# TH8_Breakout.net
KiCad netlist of a schematic drawn in Altium Designer
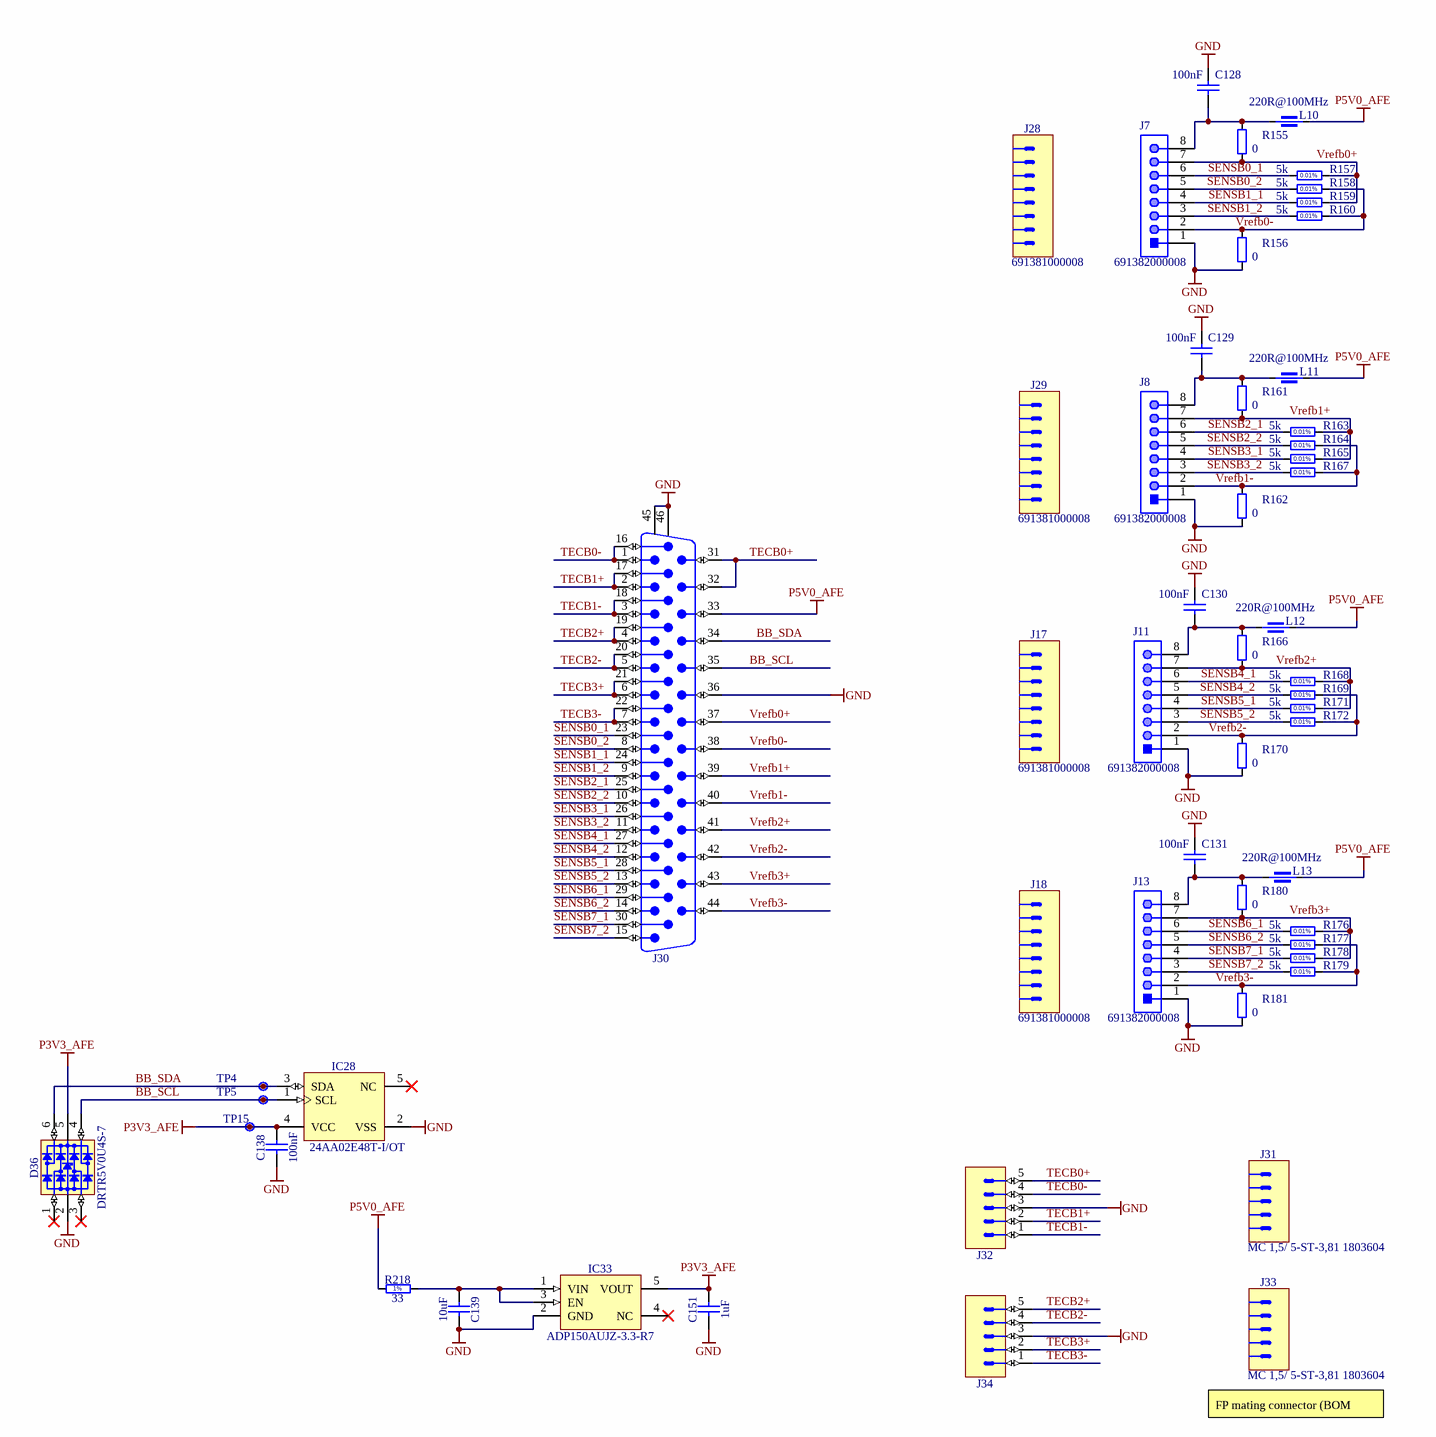
[diagram p0: TH8_Breakout.SchDoc]

(export (version "E")
  (design (tool "Eeschema 10.0.6"))
  (components
    (comp (ref "C128")
      (value "100nF")
      (footprint "CAPC1005X55N")
      (description "Non-polarised capacitor")
      (fields
        (field (name "PART NUMBER") "CC0402_100NF_16V_10%_X5R")
        (field (name "VOLTAGE") "16V")
        (field (name "AUTHOR") "CERN DEM JLC")
      )
      (libsource (lib "Capacitors") (part "Capacitor - non polarized"))
    )
    (comp (ref "C129")
      (value "100nF")
      (footprint "CAPC1005X55N")
      (description "Non-polarised capacitor")
      (fields
        (field (name "PART NUMBER") "CC0402_100NF_16V_10%_X5R")
        (field (name "VOLTAGE") "16V")
        (field (name "AUTHOR") "CERN DEM JLC")
      )
      (libsource (lib "Capacitors") (part "Capacitor - non polarized"))
    )
    (comp (ref "C130")
      (value "100nF")
      (footprint "CAPC1005X55N")
      (description "Non-polarised capacitor")
      (fields
        (field (name "PART NUMBER") "CC0402_100NF_16V_10%_X5R")
        (field (name "VOLTAGE") "16V")
        (field (name "AUTHOR") "CERN DEM JLC")
      )
      (libsource (lib "Capacitors") (part "Capacitor - non polarized"))
    )
    (comp (ref "C131")
      (value "100nF")
      (footprint "CAPC1005X55N")
      (description "Non-polarised capacitor")
      (fields
        (field (name "PART NUMBER") "CC0402_100NF_16V_10%_X5R")
        (field (name "VOLTAGE") "16V")
        (field (name "AUTHOR") "CERN DEM JLC")
      )
      (libsource (lib "Capacitors") (part "Capacitor - non polarized"))
    )
    (comp (ref "C138")
      (value "100nF")
      (footprint "CAPC1005X55N")
      (description "Non-polarised capacitor")
      (fields
        (field (name "PART NUMBER") "CC0402_100NF_16V_10%_X5R")
        (field (name "VOLTAGE") "16V")
        (field (name "AUTHOR") "CERN DEM JLC")
      )
      (libsource (lib "Capacitors") (part "Capacitor - non polarized"))
    )
    (comp (ref "C139")
      (value "10uF")
      (footprint "CAPC2012X135N")
      (description "Non-polarised capacitor")
      (fields
        (field (name "PART NUMBER") "CC0805_10UF_16V_10%_X5R")
        (field (name "VOLTAGE") "16V")
        (field (name "AUTHOR") "CERN DEM JLC")
      )
      (libsource (lib "Capacitors") (part "Capacitor - non polarized"))
    )
    (comp (ref "C151")
      (value "1uF")
      (footprint "CAPC1608X87N")
      (description "Non-polarised capacitor")
      (fields
        (field (name "PART NUMBER") "CC0603_1UF_25V_10%_X7R")
        (field (name "VOLTAGE") "25V")
        (field (name "AUTHOR") "CERN DEM JLC")
      )
      (libsource (lib "Capacitors") (part "Capacitor - non polarized"))
    )
    (comp (ref "D36")
      (value "DRTR5V0U4S-7")
      (footprint "SOT65P210X110-6N")
      (description "Integrated Quad Ultra-Low Capacitance ESD Protection")
      (fields (field (name "MANUFACTURER") "DIODES") (field (name "AUTHOR") "GK"))
      (libsource (lib "Diodes") (part "D_TVS_DRTR5V0U4S-7"))
    )
    (comp (ref "IC28")
      (value "24AA02E48T-I/OT")
      (footprint "SOT95P280X145-5N")
      (description "1.7V-5.5V, 2K I2C Serial EEPROM With EUI-48 Node Identity")
      (fields (field (name "MANUFACTURER") "MICROCHIP TECHNOLOGY") (field (name "AUTHOR") "CERN DEM MR"))
      (libsource (lib "ICs And Semiconductors") (part "24AA02E48T-I/OT"))
    )
    (comp (ref "IC33")
      (value "ADP150AUJZ-3.3-R7")
      (footprint "SOT95P280X90-5N")
      (description "Ultralow Noise, 150 mA CMOS Linear Regulator")
      (fields (field (name "MANUFACTURER") "ANALOG DEVICES") (field (name "AUTHOR") "CERN DEM JLC"))
      (libsource (lib "ICs And Semiconductors") (part "ADP150AUJZ"))
    )
    (comp (ref "J7")
      (value "691382000008")
      (footprint "691382000008")
      (description "WR-TBL Serie 382 Vertical PCB Header, Pluggable, pitch 2.5mm, 8p")
      (fields (field (name "PUBLISHER") "Wurth Elektronik"))
      (libsource (lib "Altium_WR-TBL (rev19a)") (part "691382000008"))
    )
    (comp (ref "J8")
      (value "691382000008")
      (footprint "691382000008")
      (description "WR-TBL Serie 382 Vertical PCB Header, Pluggable, pitch 2.5mm, 8p")
      (fields (field (name "PUBLISHER") "Wurth Elektronik"))
      (libsource (lib "Altium_WR-TBL (rev19a)") (part "691382000008"))
    )
    (comp (ref "J11")
      (value "691382000008")
      (footprint "691382000008")
      (description "WR-TBL Serie 382 Vertical PCB Header, Pluggable, pitch 2.5mm, 8p")
      (fields (field (name "PUBLISHER") "Wurth Elektronik"))
      (libsource (lib "Altium_WR-TBL (rev19a)") (part "691382000008"))
    )
    (comp (ref "J13")
      (value "691382000008")
      (footprint "691382000008")
      (description "WR-TBL Serie 382 Vertical PCB Header, Pluggable, pitch 2.5mm, 8p")
      (fields (field (name "PUBLISHER") "Wurth Elektronik"))
      (libsource (lib "Altium_WR-TBL (rev19a)") (part "691382000008"))
    )
    (comp (ref "J17")
      (value "691381000008")
      (footprint "WURTH_691381000008")
      (description "Phoenix Contact 2.5 pitch terminal plug, 8 ways")
      (fields (field (name "MANUFACTURER") "WURTH") (field (name "MANUFACTURER PART NUMBER") "691381000008"))
      (libsource (lib "Connectors") (part "CON_TB_WURTH_691381000008"))
    )
    (comp (ref "J18")
      (value "691381000008")
      (footprint "WURTH_691381000008")
      (description "Phoenix Contact 2.5 pitch terminal plug, 8 ways")
      (fields (field (name "MANUFACTURER") "WURTH") (field (name "MANUFACTURER PART NUMBER") "691381000008"))
      (libsource (lib "Connectors") (part "CON_TB_WURTH_691381000008"))
    )
    (comp (ref "J28")
      (value "691381000008")
      (footprint "WURTH_691381000008")
      (description "Phoenix Contact 2.5 pitch terminal plug, 8 ways")
      (fields (field (name "MANUFACTURER") "WURTH") (field (name "MANUFACTURER PART NUMBER") "691381000008"))
      (libsource (lib "Connectors") (part "CON_TB_WURTH_691381000008"))
    )
    (comp (ref "J29")
      (value "691381000008")
      (footprint "WURTH_691381000008")
      (description "Phoenix Contact 2.5 pitch terminal plug, 8 ways")
      (fields (field (name "MANUFACTURER") "WURTH") (field (name "MANUFACTURER PART NUMBER") "691381000008"))
      (libsource (lib "Connectors") (part "CON_TB_WURTH_691381000008"))
    )
    (comp (ref "J30")
      (value "D-Sub")
      (footprint "AMPHENOL_10090926-P444XLF")
      (description "Connector D-sub 44 Male")
      (fields
        (field (name "PART NUMBER") "AMPHENOL_10090926-P444XLF")
        (field (name "MANUFACTURER") "AMPHENOL")
        (field (name "AUTHOR") "CERN DEM BC")
      )
      (libsource (lib "Connectors") (part "Connector D-sub 44 Male"))
    )
    (comp (ref "J31")
      (value "~")
      (footprint "PHOENIX_1803604")
      (description "Phoenix Contact 3.81 pitch terminal plug, 5 ways")
      (fields
        (field (name "MANUFACTURER") "Phoenix Contact")
        (field (name "MANUFACTURER PART NUMBER") "MC 1,5/ 5-ST-3,81 1803604")
      )
      (libsource (lib "Connectors") (part "PHOENIX_1803604"))
    )
    (comp (ref "J32")
      (value "~")
      (footprint "PHOENIX_1803455")
      (description "Connector 5 Male")
      (fields
        (field (name "PART NUMBER") "PHOENIX_1803455")
        (field (name "MANUFACTURER") "PHOENIX CONTACT")
        (field (name "AUTHOR") "CERN DEM JLC")
      )
      (libsource (lib "Connectors") (part "Connector 5 Male"))
    )
    (comp (ref "J33")
      (value "~")
      (footprint "PHOENIX_1803604")
      (description "Phoenix Contact 3.81 pitch terminal plug, 5 ways")
      (fields
        (field (name "MANUFACTURER") "Phoenix Contact")
        (field (name "MANUFACTURER PART NUMBER") "MC 1,5/ 5-ST-3,81 1803604")
      )
      (libsource (lib "Connectors") (part "PHOENIX_1803604"))
    )
    (comp (ref "J34")
      (value "~")
      (footprint "PHOENIX_1803455")
      (description "Connector 5 Male")
      (fields
        (field (name "PART NUMBER") "PHOENIX_1803455")
        (field (name "MANUFACTURER") "PHOENIX CONTACT")
        (field (name "AUTHOR") "CERN DEM JLC")
      )
      (libsource (lib "Connectors") (part "Connector 5 Male"))
    )
    (comp (ref "L10")
      (value "220R@100MHz")
      (footprint "INDC1005X55N")
      (fields
        (field (name "PART NUMBER") "IND0402_MURATA_BLM15HB221SN1")
        (field (name "POWER") "250mA")
        (field (name "TOLERANCE") "±25%")
        (field (name "AUTHOR") "CERN DEM JLC")
      )
      (libsource (lib "Inductors & Transformers") (part "Ferrite Bead"))
    )
    (comp (ref "L11")
      (value "220R@100MHz")
      (footprint "INDC1005X55N")
      (fields
        (field (name "PART NUMBER") "IND0402_MURATA_BLM15HB221SN1")
        (field (name "POWER") "250mA")
        (field (name "TOLERANCE") "±25%")
        (field (name "AUTHOR") "CERN DEM JLC")
      )
      (libsource (lib "Inductors & Transformers") (part "Ferrite Bead"))
    )
    (comp (ref "L12")
      (value "220R@100MHz")
      (footprint "INDC1005X55N")
      (fields
        (field (name "PART NUMBER") "IND0402_MURATA_BLM15HB221SN1")
        (field (name "POWER") "250mA")
        (field (name "TOLERANCE") "±25%")
        (field (name "AUTHOR") "CERN DEM JLC")
      )
      (libsource (lib "Inductors & Transformers") (part "Ferrite Bead"))
    )
    (comp (ref "L13")
      (value "220R@100MHz")
      (footprint "INDC1005X55N")
      (fields
        (field (name "PART NUMBER") "IND0402_MURATA_BLM15HB221SN1")
        (field (name "POWER") "250mA")
        (field (name "TOLERANCE") "±25%")
        (field (name "AUTHOR") "CERN DEM JLC")
      )
      (libsource (lib "Inductors & Transformers") (part "Ferrite Bead"))
    )
    (comp (ref "R155")
      (value "0")
      (footprint "RESC1608X55N")
      (description "Resistor")
      (fields
        (field (name "PART NUMBER") "R0603_0R_JUMPER")
        (field (name "MANUFACTURER") "GENERIC")
        (field (name "AUTHOR") "CERN DEM JLC")
      )
      (libsource (lib "Resistors") (part "Resistor"))
    )
    (comp (ref "R156")
      (value "0")
      (footprint "RESC1608X55N")
      (description "Resistor")
      (fields
        (field (name "PART NUMBER") "R0603_0R_JUMPER")
        (field (name "MANUFACTURER") "GENERIC")
        (field (name "AUTHOR") "CERN DEM JLC")
      )
      (libsource (lib "Resistors") (part "Resistor"))
    )
    (comp (ref "R157")
      (value "5k")
      (footprint "RESC2013X64N")
      (description "Resistor - 0.01%")
      (fields
        (field (name "PART NUMBER") "R0805_5K_0.01%_0.2W_0.2PPM_VISHAY_VSMP")
        (field (name "POWER") "0.2W")
        (field (name "AUTHOR") "CERN DEM JLC")
      )
      (libsource (lib "Resistors") (part "Resistor - 0.01%"))
    )
    (comp (ref "R158")
      (value "5k")
      (footprint "RESC2013X64N")
      (description "Resistor - 0.01%")
      (fields
        (field (name "PART NUMBER") "R0805_5K_0.01%_0.2W_0.2PPM_VISHAY_VSMP")
        (field (name "POWER") "0.2W")
        (field (name "AUTHOR") "CERN DEM JLC")
      )
      (libsource (lib "Resistors") (part "Resistor - 0.01%"))
    )
    (comp (ref "R159")
      (value "5k")
      (footprint "RESC2013X64N")
      (description "Resistor - 0.01%")
      (fields
        (field (name "PART NUMBER") "R0805_5K_0.01%_0.2W_0.2PPM_VISHAY_VSMP")
        (field (name "POWER") "0.2W")
        (field (name "AUTHOR") "CERN DEM JLC")
      )
      (libsource (lib "Resistors") (part "Resistor - 0.01%"))
    )
    (comp (ref "R160")
      (value "5k")
      (footprint "RESC2013X64N")
      (description "Resistor - 0.01%")
      (fields
        (field (name "PART NUMBER") "R0805_5K_0.01%_0.2W_0.2PPM_VISHAY_VSMP")
        (field (name "POWER") "0.2W")
        (field (name "AUTHOR") "CERN DEM JLC")
      )
      (libsource (lib "Resistors") (part "Resistor - 0.01%"))
    )
    (comp (ref "R161")
      (value "0")
      (footprint "RESC1608X55N")
      (description "Resistor")
      (fields
        (field (name "PART NUMBER") "R0603_0R_JUMPER")
        (field (name "MANUFACTURER") "GENERIC")
        (field (name "AUTHOR") "CERN DEM JLC")
      )
      (libsource (lib "Resistors") (part "Resistor"))
    )
    (comp (ref "R162")
      (value "0")
      (footprint "RESC1608X55N")
      (description "Resistor")
      (fields
        (field (name "PART NUMBER") "R0603_0R_JUMPER")
        (field (name "MANUFACTURER") "GENERIC")
        (field (name "AUTHOR") "CERN DEM JLC")
      )
      (libsource (lib "Resistors") (part "Resistor"))
    )
    (comp (ref "R163")
      (value "5k")
      (footprint "RESC2013X64N")
      (description "Resistor - 0.01%")
      (fields
        (field (name "PART NUMBER") "R0805_5K_0.01%_0.2W_0.2PPM_VISHAY_VSMP")
        (field (name "POWER") "0.2W")
        (field (name "AUTHOR") "CERN DEM JLC")
      )
      (libsource (lib "Resistors") (part "Resistor - 0.01%"))
    )
    (comp (ref "R164")
      (value "5k")
      (footprint "RESC2013X64N")
      (description "Resistor - 0.01%")
      (fields
        (field (name "PART NUMBER") "R0805_5K_0.01%_0.2W_0.2PPM_VISHAY_VSMP")
        (field (name "POWER") "0.2W")
        (field (name "AUTHOR") "CERN DEM JLC")
      )
      (libsource (lib "Resistors") (part "Resistor - 0.01%"))
    )
    (comp (ref "R165")
      (value "5k")
      (footprint "RESC2013X64N")
      (description "Resistor - 0.01%")
      (fields
        (field (name "PART NUMBER") "R0805_5K_0.01%_0.2W_0.2PPM_VISHAY_VSMP")
        (field (name "POWER") "0.2W")
        (field (name "AUTHOR") "CERN DEM JLC")
      )
      (libsource (lib "Resistors") (part "Resistor - 0.01%"))
    )
    (comp (ref "R166")
      (value "0")
      (footprint "RESC1608X55N")
      (description "Resistor")
      (fields
        (field (name "PART NUMBER") "R0603_0R_JUMPER")
        (field (name "MANUFACTURER") "GENERIC")
        (field (name "AUTHOR") "CERN DEM JLC")
      )
      (libsource (lib "Resistors") (part "Resistor"))
    )
    (comp (ref "R167")
      (value "5k")
      (footprint "RESC2013X64N")
      (description "Resistor - 0.01%")
      (fields
        (field (name "PART NUMBER") "R0805_5K_0.01%_0.2W_0.2PPM_VISHAY_VSMP")
        (field (name "POWER") "0.2W")
        (field (name "AUTHOR") "CERN DEM JLC")
      )
      (libsource (lib "Resistors") (part "Resistor - 0.01%"))
    )
    (comp (ref "R168")
      (value "5k")
      (footprint "RESC2013X64N")
      (description "Resistor - 0.01%")
      (fields
        (field (name "PART NUMBER") "R0805_5K_0.01%_0.2W_0.2PPM_VISHAY_VSMP")
        (field (name "POWER") "0.2W")
        (field (name "AUTHOR") "CERN DEM JLC")
      )
      (libsource (lib "Resistors") (part "Resistor - 0.01%"))
    )
    (comp (ref "R169")
      (value "5k")
      (footprint "RESC2013X64N")
      (description "Resistor - 0.01%")
      (fields
        (field (name "PART NUMBER") "R0805_5K_0.01%_0.2W_0.2PPM_VISHAY_VSMP")
        (field (name "POWER") "0.2W")
        (field (name "AUTHOR") "CERN DEM JLC")
      )
      (libsource (lib "Resistors") (part "Resistor - 0.01%"))
    )
    (comp (ref "R170")
      (value "0")
      (footprint "RESC1608X55N")
      (description "Resistor")
      (fields
        (field (name "PART NUMBER") "R0603_0R_JUMPER")
        (field (name "MANUFACTURER") "GENERIC")
        (field (name "AUTHOR") "CERN DEM JLC")
      )
      (libsource (lib "Resistors") (part "Resistor"))
    )
    (comp (ref "R171")
      (value "5k")
      (footprint "RESC2013X64N")
      (description "Resistor - 0.01%")
      (fields
        (field (name "PART NUMBER") "R0805_5K_0.01%_0.2W_0.2PPM_VISHAY_VSMP")
        (field (name "POWER") "0.2W")
        (field (name "AUTHOR") "CERN DEM JLC")
      )
      (libsource (lib "Resistors") (part "Resistor - 0.01%"))
    )
    (comp (ref "R172")
      (value "5k")
      (footprint "RESC2013X64N")
      (description "Resistor - 0.01%")
      (fields
        (field (name "PART NUMBER") "R0805_5K_0.01%_0.2W_0.2PPM_VISHAY_VSMP")
        (field (name "POWER") "0.2W")
        (field (name "AUTHOR") "CERN DEM JLC")
      )
      (libsource (lib "Resistors") (part "Resistor - 0.01%"))
    )
    (comp (ref "R176")
      (value "5k")
      (footprint "RESC2013X64N")
      (description "Resistor - 0.01%")
      (fields
        (field (name "PART NUMBER") "R0805_5K_0.01%_0.2W_0.2PPM_VISHAY_VSMP")
        (field (name "POWER") "0.2W")
        (field (name "AUTHOR") "CERN DEM JLC")
      )
      (libsource (lib "Resistors") (part "Resistor - 0.01%"))
    )
    (comp (ref "R177")
      (value "5k")
      (footprint "RESC2013X64N")
      (description "Resistor - 0.01%")
      (fields
        (field (name "PART NUMBER") "R0805_5K_0.01%_0.2W_0.2PPM_VISHAY_VSMP")
        (field (name "POWER") "0.2W")
        (field (name "AUTHOR") "CERN DEM JLC")
      )
      (libsource (lib "Resistors") (part "Resistor - 0.01%"))
    )
    (comp (ref "R178")
      (value "5k")
      (footprint "RESC2013X64N")
      (description "Resistor - 0.01%")
      (fields
        (field (name "PART NUMBER") "R0805_5K_0.01%_0.2W_0.2PPM_VISHAY_VSMP")
        (field (name "POWER") "0.2W")
        (field (name "AUTHOR") "CERN DEM JLC")
      )
      (libsource (lib "Resistors") (part "Resistor - 0.01%"))
    )
    (comp (ref "R179")
      (value "5k")
      (footprint "RESC2013X64N")
      (description "Resistor - 0.01%")
      (fields
        (field (name "PART NUMBER") "R0805_5K_0.01%_0.2W_0.2PPM_VISHAY_VSMP")
        (field (name "POWER") "0.2W")
        (field (name "AUTHOR") "CERN DEM JLC")
      )
      (libsource (lib "Resistors") (part "Resistor - 0.01%"))
    )
    (comp (ref "R180")
      (value "0")
      (footprint "RESC1608X55N")
      (description "Resistor")
      (fields
        (field (name "PART NUMBER") "R0603_0R_JUMPER")
        (field (name "MANUFACTURER") "GENERIC")
        (field (name "AUTHOR") "CERN DEM JLC")
      )
      (libsource (lib "Resistors") (part "Resistor"))
    )
    (comp (ref "R181")
      (value "0")
      (footprint "RESC1608X55N")
      (description "Resistor")
      (fields
        (field (name "PART NUMBER") "R0603_0R_JUMPER")
        (field (name "MANUFACTURER") "GENERIC")
        (field (name "AUTHOR") "CERN DEM JLC")
      )
      (libsource (lib "Resistors") (part "Resistor"))
    )
    (comp (ref "R218")
      (value "33")
      (footprint "RESC1005X40N")
      (description "Resistor - 1%")
      (fields
        (field (name "PART NUMBER") "R0402_33R_1%_0.0625W_100PPM")
        (field (name "POWER") "0.0625W")
        (field (name "AUTHOR") "CERN DEM JLC")
      )
      (libsource (lib "Resistors") (part "Resistor - 1%"))
    )
    (comp (ref "TP4")
      (value "Test Point")
      (footprint "TPS127")
      (fields (field (name "PART NUMBER") "SMD_PAD_1.27X1.27MM") (field (name "AUTHOR") "CERN DEM JLC"))
      (libsource (lib "Eletro-mechanical") (part "Test Point"))
    )
    (comp (ref "TP5")
      (value "Test Point")
      (footprint "TPS127")
      (fields (field (name "PART NUMBER") "SMD_PAD_1.27X1.27MM") (field (name "AUTHOR") "CERN DEM JLC"))
      (libsource (lib "Eletro-mechanical") (part "Test Point"))
    )
    (comp (ref "TP15")
      (value "Test Point")
      (footprint "TPS127")
      (fields (field (name "PART NUMBER") "SMD_PAD_1.27X1.27MM") (field (name "AUTHOR") "CERN DEM JLC"))
      (libsource (lib "Eletro-mechanical") (part "Test Point"))
    )
  )
  (nets
    (net (code "1") (name "/BB_SCL") (class "Default")
      (node (ref "D36") (pin "4") (pinfunction "I/O3_4") (pintype "bidirectional"))
      (node (ref "IC28") (pin "1") (pinfunction "SCL_1") (pintype "input"))
      (node (ref "J30") (pin "35") (pinfunction "35_35") (pintype "bidirectional"))
      (node (ref "TP5") (pin "1") (pinfunction "1_1") (pintype "bidirectional"))
    )
    (net (code "2") (name "/BB_SDA") (class "Default")
      (node (ref "D36") (pin "6") (pinfunction "I/O4_6") (pintype "bidirectional"))
      (node (ref "IC28") (pin "3") (pinfunction "SDA_3") (pintype "bidirectional"))
      (node (ref "J30") (pin "34") (pinfunction "34_34") (pintype "bidirectional"))
      (node (ref "TP4") (pin "1") (pinfunction "1_1") (pintype "bidirectional"))
    )
    (net (code "3") (name "/SENSB0_1") (class "Default")
      (node (ref "J30") (pin "23") (pinfunction "23_23") (pintype "bidirectional"))
      (node (ref "J7") (pin "6") (pinfunction "6_6") (pintype "passive"))
      (node (ref "R157") (pin "1") (pinfunction "1_1") (pintype "passive"))
    )
    (net (code "4") (name "/SENSB0_2") (class "Default")
      (node (ref "J30") (pin "8") (pinfunction "8_8") (pintype "bidirectional"))
      (node (ref "J7") (pin "5") (pinfunction "5_5") (pintype "passive"))
      (node (ref "R158") (pin "1") (pinfunction "1_1") (pintype "passive"))
    )
    (net (code "5") (name "/SENSB1_1") (class "Default")
      (node (ref "J30") (pin "24") (pinfunction "24_24") (pintype "bidirectional"))
      (node (ref "J7") (pin "4") (pinfunction "4_4") (pintype "passive"))
      (node (ref "R159") (pin "1") (pinfunction "1_1") (pintype "passive"))
    )
    (net (code "6") (name "/SENSB1_2") (class "Default")
      (node (ref "J30") (pin "9") (pinfunction "9_9") (pintype "bidirectional"))
      (node (ref "J7") (pin "3") (pinfunction "3_3") (pintype "passive"))
      (node (ref "R160") (pin "1") (pinfunction "1_1") (pintype "passive"))
    )
    (net (code "7") (name "/SENSB2_1") (class "Default")
      (node (ref "J30") (pin "25") (pinfunction "25_25") (pintype "bidirectional"))
      (node (ref "J8") (pin "6") (pinfunction "6_6") (pintype "passive"))
      (node (ref "R163") (pin "1") (pinfunction "1_1") (pintype "passive"))
    )
    (net (code "8") (name "/SENSB2_2") (class "Default")
      (node (ref "J30") (pin "10") (pinfunction "10_10") (pintype "bidirectional"))
      (node (ref "J8") (pin "5") (pinfunction "5_5") (pintype "passive"))
      (node (ref "R164") (pin "1") (pinfunction "1_1") (pintype "passive"))
    )
    (net (code "9") (name "/SENSB3_1") (class "Default")
      (node (ref "J30") (pin "26") (pinfunction "26_26") (pintype "bidirectional"))
      (node (ref "J8") (pin "4") (pinfunction "4_4") (pintype "passive"))
      (node (ref "R165") (pin "1") (pinfunction "1_1") (pintype "passive"))
    )
    (net (code "10") (name "/SENSB3_2") (class "Default")
      (node (ref "J30") (pin "11") (pinfunction "11_11") (pintype "bidirectional"))
      (node (ref "J8") (pin "3") (pinfunction "3_3") (pintype "passive"))
      (node (ref "R167") (pin "1") (pinfunction "1_1") (pintype "passive"))
    )
    (net (code "11") (name "/SENSB4_1") (class "Default")
      (node (ref "J11") (pin "6") (pinfunction "6_6") (pintype "passive"))
      (node (ref "J30") (pin "27") (pinfunction "27_27") (pintype "bidirectional"))
      (node (ref "R168") (pin "1") (pinfunction "1_1") (pintype "passive"))
    )
    (net (code "12") (name "/SENSB4_2") (class "Default")
      (node (ref "J11") (pin "5") (pinfunction "5_5") (pintype "passive"))
      (node (ref "J30") (pin "12") (pinfunction "12_12") (pintype "bidirectional"))
      (node (ref "R169") (pin "1") (pinfunction "1_1") (pintype "passive"))
    )
    (net (code "13") (name "/SENSB5_1") (class "Default")
      (node (ref "J11") (pin "4") (pinfunction "4_4") (pintype "passive"))
      (node (ref "J30") (pin "28") (pinfunction "28_28") (pintype "bidirectional"))
      (node (ref "R171") (pin "1") (pinfunction "1_1") (pintype "passive"))
    )
    (net (code "14") (name "/SENSB5_2") (class "Default")
      (node (ref "J11") (pin "3") (pinfunction "3_3") (pintype "passive"))
      (node (ref "J30") (pin "13") (pinfunction "13_13") (pintype "bidirectional"))
      (node (ref "R172") (pin "1") (pinfunction "1_1") (pintype "passive"))
    )
    (net (code "15") (name "/SENSB6_1") (class "Default")
      (node (ref "J13") (pin "6") (pinfunction "6_6") (pintype "passive"))
      (node (ref "J30") (pin "29") (pinfunction "29_29") (pintype "bidirectional"))
      (node (ref "R176") (pin "1") (pinfunction "1_1") (pintype "passive"))
    )
    (net (code "16") (name "/SENSB6_2") (class "Default")
      (node (ref "J13") (pin "5") (pinfunction "5_5") (pintype "passive"))
      (node (ref "J30") (pin "14") (pinfunction "14_14") (pintype "bidirectional"))
      (node (ref "R177") (pin "1") (pinfunction "1_1") (pintype "passive"))
    )
    (net (code "17") (name "/SENSB7_1") (class "Default")
      (node (ref "J13") (pin "4") (pinfunction "4_4") (pintype "passive"))
      (node (ref "J30") (pin "30") (pinfunction "30_30") (pintype "bidirectional"))
      (node (ref "R178") (pin "1") (pinfunction "1_1") (pintype "passive"))
    )
    (net (code "18") (name "/SENSB7_2") (class "Default")
      (node (ref "J13") (pin "3") (pinfunction "3_3") (pintype "passive"))
      (node (ref "J30") (pin "15") (pinfunction "15_15") (pintype "bidirectional"))
      (node (ref "R179") (pin "1") (pinfunction "1_1") (pintype "passive"))
    )
    (net (code "19") (name "/TECB0+") (class "Default")
      (node (ref "J30") (pin "31") (pinfunction "31_31") (pintype "bidirectional"))
      (node (ref "J30") (pin "32") (pinfunction "32_32") (pintype "bidirectional"))
      (node (ref "J32") (pin "5") (pinfunction "5_5") (pintype "bidirectional"))
    )
    (net (code "20") (name "/TECB0-") (class "Default")
      (node (ref "J30") (pin "1") (pinfunction "1_1") (pintype "bidirectional"))
      (node (ref "J30") (pin "16") (pinfunction "16_16") (pintype "bidirectional"))
      (node (ref "J32") (pin "4") (pinfunction "4_4") (pintype "bidirectional"))
    )
    (net (code "21") (name "/TECB1+") (class "Default")
      (node (ref "J30") (pin "17") (pinfunction "17_17") (pintype "bidirectional"))
      (node (ref "J30") (pin "2") (pinfunction "2_2") (pintype "bidirectional"))
      (node (ref "J32") (pin "2") (pinfunction "2_2") (pintype "bidirectional"))
    )
    (net (code "22") (name "/TECB1-") (class "Default")
      (node (ref "J30") (pin "18") (pinfunction "18_18") (pintype "bidirectional"))
      (node (ref "J30") (pin "3") (pinfunction "3_3") (pintype "bidirectional"))
      (node (ref "J32") (pin "1") (pinfunction "1_1") (pintype "bidirectional"))
    )
    (net (code "23") (name "/TECB2+") (class "Default")
      (node (ref "J30") (pin "19") (pinfunction "19_19") (pintype "bidirectional"))
      (node (ref "J30") (pin "4") (pinfunction "4_4") (pintype "bidirectional"))
      (node (ref "J34") (pin "5") (pinfunction "5_5") (pintype "bidirectional"))
    )
    (net (code "24") (name "/TECB2-") (class "Default")
      (node (ref "J30") (pin "20") (pinfunction "20_20") (pintype "bidirectional"))
      (node (ref "J30") (pin "5") (pinfunction "5_5") (pintype "bidirectional"))
      (node (ref "J34") (pin "4") (pinfunction "4_4") (pintype "bidirectional"))
    )
    (net (code "25") (name "/TECB3+") (class "Default")
      (node (ref "J30") (pin "21") (pinfunction "21_21") (pintype "bidirectional"))
      (node (ref "J30") (pin "6") (pinfunction "6_6") (pintype "bidirectional"))
      (node (ref "J34") (pin "2") (pinfunction "2_2") (pintype "bidirectional"))
    )
    (net (code "26") (name "/TECB3-") (class "Default")
      (node (ref "J30") (pin "22") (pinfunction "22_22") (pintype "bidirectional"))
      (node (ref "J30") (pin "7") (pinfunction "7_7") (pintype "bidirectional"))
      (node (ref "J34") (pin "1") (pinfunction "1_1") (pintype "bidirectional"))
    )
    (net (code "27") (name "/Vrefb0+") (class "Default")
      (node (ref "J30") (pin "37") (pinfunction "37_37") (pintype "bidirectional"))
      (node (ref "J7") (pin "7") (pinfunction "7_7") (pintype "passive"))
      (node (ref "R155") (pin "1") (pinfunction "1_1") (pintype "passive"))
      (node (ref "R157") (pin "2") (pinfunction "2_2") (pintype "passive"))
      (node (ref "R159") (pin "2") (pinfunction "2_2") (pintype "passive"))
    )
    (net (code "28") (name "/Vrefb0-") (class "Default")
      (node (ref "J30") (pin "38") (pinfunction "38_38") (pintype "bidirectional"))
      (node (ref "J7") (pin "2") (pinfunction "2_2") (pintype "passive"))
      (node (ref "R156") (pin "2") (pinfunction "2_2") (pintype "passive"))
      (node (ref "R158") (pin "2") (pinfunction "2_2") (pintype "passive"))
      (node (ref "R160") (pin "2") (pinfunction "2_2") (pintype "passive"))
    )
    (net (code "29") (name "/Vrefb1+") (class "Default")
      (node (ref "J30") (pin "39") (pinfunction "39_39") (pintype "bidirectional"))
      (node (ref "J8") (pin "7") (pinfunction "7_7") (pintype "passive"))
      (node (ref "R161") (pin "1") (pinfunction "1_1") (pintype "passive"))
      (node (ref "R163") (pin "2") (pinfunction "2_2") (pintype "passive"))
      (node (ref "R165") (pin "2") (pinfunction "2_2") (pintype "passive"))
    )
    (net (code "30") (name "/Vrefb1-") (class "Default")
      (node (ref "J30") (pin "40") (pinfunction "40_40") (pintype "bidirectional"))
      (node (ref "J8") (pin "2") (pinfunction "2_2") (pintype "passive"))
      (node (ref "R162") (pin "2") (pinfunction "2_2") (pintype "passive"))
      (node (ref "R164") (pin "2") (pinfunction "2_2") (pintype "passive"))
      (node (ref "R167") (pin "2") (pinfunction "2_2") (pintype "passive"))
    )
    (net (code "31") (name "/Vrefb2+") (class "Default")
      (node (ref "J11") (pin "7") (pinfunction "7_7") (pintype "passive"))
      (node (ref "J30") (pin "41") (pinfunction "41_41") (pintype "bidirectional"))
      (node (ref "R166") (pin "1") (pinfunction "1_1") (pintype "passive"))
      (node (ref "R168") (pin "2") (pinfunction "2_2") (pintype "passive"))
      (node (ref "R171") (pin "2") (pinfunction "2_2") (pintype "passive"))
    )
    (net (code "32") (name "/Vrefb2-") (class "Default")
      (node (ref "J11") (pin "2") (pinfunction "2_2") (pintype "passive"))
      (node (ref "J30") (pin "42") (pinfunction "42_42") (pintype "bidirectional"))
      (node (ref "R169") (pin "2") (pinfunction "2_2") (pintype "passive"))
      (node (ref "R170") (pin "2") (pinfunction "2_2") (pintype "passive"))
      (node (ref "R172") (pin "2") (pinfunction "2_2") (pintype "passive"))
    )
    (net (code "33") (name "/Vrefb3+") (class "Default")
      (node (ref "J13") (pin "7") (pinfunction "7_7") (pintype "passive"))
      (node (ref "J30") (pin "43") (pinfunction "43_43") (pintype "bidirectional"))
      (node (ref "R176") (pin "2") (pinfunction "2_2") (pintype "passive"))
      (node (ref "R178") (pin "2") (pinfunction "2_2") (pintype "passive"))
      (node (ref "R180") (pin "1") (pinfunction "1_1") (pintype "passive"))
    )
    (net (code "34") (name "/Vrefb3-") (class "Default")
      (node (ref "J13") (pin "2") (pinfunction "2_2") (pintype "passive"))
      (node (ref "J30") (pin "44") (pinfunction "44_44") (pintype "bidirectional"))
      (node (ref "R177") (pin "2") (pinfunction "2_2") (pintype "passive"))
      (node (ref "R179") (pin "2") (pinfunction "2_2") (pintype "passive"))
      (node (ref "R181") (pin "2") (pinfunction "2_2") (pintype "passive"))
    )
    (net (code "35") (name "GND") (class "Default")
      (node (ref "C128") (pin "1") (pinfunction "1_1") (pintype "passive"))
      (node (ref "C129") (pin "1") (pinfunction "1_1") (pintype "passive"))
      (node (ref "C130") (pin "1") (pinfunction "1_1") (pintype "passive"))
      (node (ref "C131") (pin "1") (pinfunction "1_1") (pintype "passive"))
      (node (ref "C138") (pin "1") (pinfunction "1_1") (pintype "passive"))
      (node (ref "C139") (pin "2") (pinfunction "2_2") (pintype "passive"))
      (node (ref "C151") (pin "1") (pinfunction "1_1") (pintype "passive"))
      (node (ref "D36") (pin "2") (pinfunction "GND_2") (pintype "power_in"))
      (node (ref "IC28") (pin "2") (pinfunction "VSS_2") (pintype "power_in"))
      (node (ref "IC33") (pin "2") (pinfunction "GND_2") (pintype "power_in"))
      (node (ref "J11") (pin "1") (pinfunction "1_1") (pintype "passive"))
      (node (ref "J13") (pin "1") (pinfunction "1_1") (pintype "passive"))
      (node (ref "J30") (pin "36") (pinfunction "36_36") (pintype "bidirectional"))
      (node (ref "J30") (pin "45") (pinfunction "45_45") (pintype "passive"))
      (node (ref "J30") (pin "46") (pinfunction "46_46") (pintype "passive"))
      (node (ref "J32") (pin "3") (pinfunction "3_3") (pintype "bidirectional"))
      (node (ref "J34") (pin "3") (pinfunction "3_3") (pintype "bidirectional"))
      (node (ref "J7") (pin "1") (pinfunction "1_1") (pintype "passive"))
      (node (ref "J8") (pin "1") (pinfunction "1_1") (pintype "passive"))
      (node (ref "R156") (pin "1") (pinfunction "1_1") (pintype "passive"))
      (node (ref "R162") (pin "1") (pinfunction "1_1") (pintype "passive"))
      (node (ref "R170") (pin "1") (pinfunction "1_1") (pintype "passive"))
      (node (ref "R181") (pin "1") (pinfunction "1_1") (pintype "passive"))
    )
    (net (code "36") (name "Net-(C128-Pad2)") (class "Default")
      (node (ref "C128") (pin "2") (pinfunction "2_2") (pintype "passive"))
      (node (ref "J7") (pin "8") (pinfunction "8_8") (pintype "passive"))
      (node (ref "L10") (pin "1") (pinfunction "1_1") (pintype "passive"))
      (node (ref "R155") (pin "2") (pinfunction "2_2") (pintype "passive"))
    )
    (net (code "37") (name "Net-(C129-Pad2)") (class "Default")
      (node (ref "C129") (pin "2") (pinfunction "2_2") (pintype "passive"))
      (node (ref "J8") (pin "8") (pinfunction "8_8") (pintype "passive"))
      (node (ref "L11") (pin "1") (pinfunction "1_1") (pintype "passive"))
      (node (ref "R161") (pin "2") (pinfunction "2_2") (pintype "passive"))
    )
    (net (code "38") (name "Net-(C130-Pad2)") (class "Default")
      (node (ref "C130") (pin "2") (pinfunction "2_2") (pintype "passive"))
      (node (ref "J11") (pin "8") (pinfunction "8_8") (pintype "passive"))
      (node (ref "L12") (pin "1") (pinfunction "1_1") (pintype "passive"))
      (node (ref "R166") (pin "2") (pinfunction "2_2") (pintype "passive"))
    )
    (net (code "39") (name "Net-(C131-Pad2)") (class "Default")
      (node (ref "C131") (pin "2") (pinfunction "2_2") (pintype "passive"))
      (node (ref "J13") (pin "8") (pinfunction "8_8") (pintype "passive"))
      (node (ref "L13") (pin "1") (pinfunction "1_1") (pintype "passive"))
      (node (ref "R180") (pin "2") (pinfunction "2_2") (pintype "passive"))
    )
    (net (code "40") (name "Net-(IC33-EN)") (class "Default")
      (node (ref "C139") (pin "1") (pinfunction "1_1") (pintype "passive"))
      (node (ref "IC33") (pin "1") (pinfunction "VIN_1") (pintype "input"))
      (node (ref "IC33") (pin "3") (pinfunction "EN_3") (pintype "input"))
      (node (ref "R218") (pin "2") (pinfunction "2_2") (pintype "passive"))
    )
    (net (code "41") (name "P3V3_AFE") (class "Default")
      (node (ref "C138") (pin "2") (pinfunction "2_2") (pintype "passive"))
      (node (ref "C151") (pin "2") (pinfunction "2_2") (pintype "passive"))
      (node (ref "D36") (pin "5") (pinfunction "VBUS_5") (pintype "power_in"))
      (node (ref "IC28") (pin "4") (pinfunction "VCC_4") (pintype "power_in"))
      (node (ref "IC33") (pin "5") (pinfunction "VOUT_5") (pintype "power_in"))
      (node (ref "TP15") (pin "1") (pinfunction "1_1") (pintype "bidirectional"))
    )
    (net (code "42") (name "P5V0_AFE") (class "Default")
      (node (ref "J30") (pin "33") (pinfunction "33_33") (pintype "bidirectional"))
      (node (ref "L10") (pin "2") (pinfunction "2_2") (pintype "passive"))
      (node (ref "L11") (pin "2") (pinfunction "2_2") (pintype "passive"))
      (node (ref "L12") (pin "2") (pinfunction "2_2") (pintype "passive"))
      (node (ref "L13") (pin "2") (pinfunction "2_2") (pintype "passive"))
      (node (ref "R218") (pin "1") (pinfunction "1_1") (pintype "passive"))
    )
    (net (code "43") (name "unconnected-(D36-I{slash}O1-Pad1)") (class "Default")
      (node (ref "D36") (pin "1") (pinfunction "I/O1_1") (pintype "bidirectional+no_connect"))
    )
    (net (code "44") (name "unconnected-(D36-I{slash}O2-Pad3)") (class "Default")
      (node (ref "D36") (pin "3") (pinfunction "I/O2_3") (pintype "bidirectional+no_connect"))
    )
    (net (code "45") (name "unconnected-(IC28-NC-Pad5)") (class "Default")
      (node (ref "IC28") (pin "5") (pinfunction "NC_5") (pintype "passive+no_connect"))
    )
    (net (code "46") (name "unconnected-(IC33-NC-Pad4)") (class "Default")
      (node (ref "IC33") (pin "4") (pinfunction "NC_4") (pintype "passive+no_connect"))
    )
  )
)
